# Nestling_2_1_EXB_MPU6050.net
KiCad netlist of a schematic drawn in Altium Designer
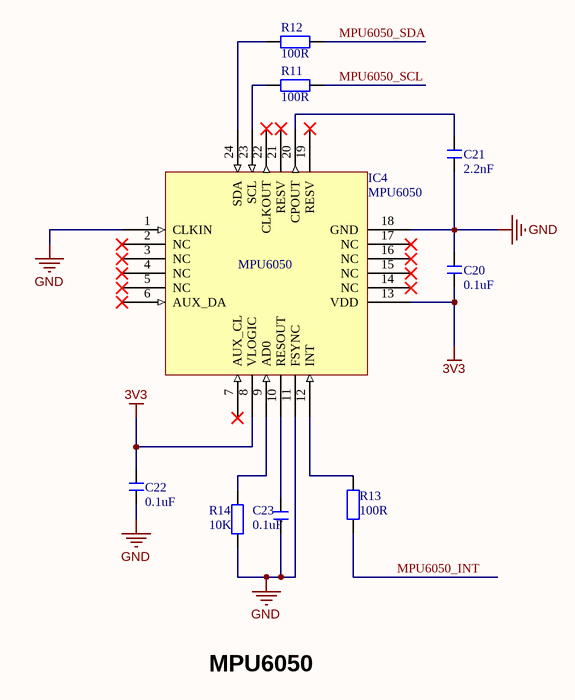
[diagram p0: Nestling_2.1_EXB_MPU6050.SchDoc]

(export (version "E")
  (design (tool "Eeschema 10.0.6"))
  (components
    (comp (ref "C20")
      (value "0.1uF")
      (footprint "C 0603_M")
      (description "无极性贴片电容")
      (fields (field (name "版权归属") "源创客"))
      (libsource (lib "altium-import") (part "root_3_C_"))
    )
    (comp (ref "C21")
      (value "2.2nF")
      (footprint "C 0603_M")
      (description "无极性贴片电容")
      (fields (field (name "版权归属") "源创客"))
      (libsource (lib "altium-import") (part "root_3_C_"))
    )
    (comp (ref "C22")
      (value "0.1uF")
      (footprint "C 0603_M")
      (description "无极性贴片电容")
      (fields (field (name "版权归属") "源创客"))
      (libsource (lib "altium-import") (part "root_3_C_"))
    )
    (comp (ref "C23")
      (value "0.1uF")
      (footprint "C 0603_M")
      (description "无极性贴片电容")
      (fields (field (name "版权归属") "源创客"))
      (libsource (lib "altium-import") (part "root_3_C_"))
    )
    (comp (ref "IC4")
      (value "MPU6050")
      (footprint "QFN24 4x4_N")
      (libsource (lib "altium-import") (part "root_0_MPU6050_"))
    )
    (comp (ref "R11")
      (value "100R")
      (footprint "R 0603_M")
      (description "Resistor")
      (libsource (lib "") (part "RES_1"))
    )
    (comp (ref "R12")
      (value "100R")
      (footprint "R 0603_M")
      (description "Resistor")
      (libsource (lib "") (part "RES_1"))
    )
    (comp (ref "R13")
      (value "100R")
      (footprint "R 0603_M")
      (description "Resistor")
      (libsource (lib "General") (part "RES"))
    )
    (comp (ref "R14")
      (value "10K")
      (footprint "R 0603_M")
      (description "Resistor")
      (libsource (lib "") (part "RES_2"))
    )
  )
  (nets
    (net (code "1") (name "/MPU6050_INT") (class "Default")
      (node (ref "R13") (pin "1") (pinfunction "1_1") (pintype "passive"))
    )
    (net (code "2") (name "/MPU6050_SCL") (class "Default")
      (node (ref "R11") (pin "1") (pinfunction "1_1") (pintype "passive"))
    )
    (net (code "3") (name "/MPU6050_SDA") (class "Default")
      (node (ref "R12") (pin "1") (pinfunction "1_1") (pintype "passive"))
    )
    (net (code "4") (name "3V3") (class "Default")
      (node (ref "C20") (pin "2") (pinfunction "2_2") (pintype "passive"))
      (node (ref "C22") (pin "1") (pinfunction "1_1") (pintype "passive"))
      (node (ref "IC4") (pin "13") (pinfunction "VDD_13") (pintype "power_in"))
      (node (ref "IC4") (pin "8") (pinfunction "VLOGIC_8") (pintype "passive"))
    )
    (net (code "5") (name "GND") (class "Default")
      (node (ref "C20") (pin "1") (pinfunction "1_1") (pintype "passive"))
      (node (ref "C21") (pin "2") (pinfunction "2_2") (pintype "passive"))
      (node (ref "C22") (pin "2") (pinfunction "2_2") (pintype "passive"))
      (node (ref "C23") (pin "2") (pinfunction "2_2") (pintype "passive"))
      (node (ref "IC4") (pin "1") (pinfunction "CLKIN_1") (pintype "input"))
      (node (ref "IC4") (pin "11") (pinfunction "FSYNC_11") (pintype "passive"))
      (node (ref "IC4") (pin "18") (pinfunction "GND_18") (pintype "power_in"))
      (node (ref "R14") (pin "2") (pinfunction "2_2") (pintype "passive"))
    )
    (net (code "6") (name "Net-(IC4-AD0)") (class "Default")
      (node (ref "IC4") (pin "9") (pinfunction "AD0_9") (pintype "input"))
      (node (ref "R14") (pin "1") (pinfunction "1_1") (pintype "passive"))
    )
    (net (code "7") (name "Net-(IC4-CPOUT)") (class "Default")
      (node (ref "C21") (pin "1") (pinfunction "1_1") (pintype "passive"))
      (node (ref "IC4") (pin "20") (pinfunction "CPOUT_20") (pintype "output"))
    )
    (net (code "8") (name "Net-(IC4-INT)") (class "Default")
      (node (ref "IC4") (pin "12") (pinfunction "INT_12") (pintype "input"))
      (node (ref "R13") (pin "2") (pinfunction "2_2") (pintype "passive"))
    )
    (net (code "9") (name "Net-(IC4-RESOUT)") (class "Default")
      (node (ref "C23") (pin "1") (pinfunction "1_1") (pintype "passive"))
      (node (ref "IC4") (pin "10") (pinfunction "RESOUT_10") (pintype "passive"))
    )
    (net (code "10") (name "Net-(IC4-SCL)") (class "Default")
      (node (ref "IC4") (pin "23") (pinfunction "SCL_23") (pintype "input"))
      (node (ref "R11") (pin "2") (pinfunction "2_2") (pintype "passive"))
    )
    (net (code "11") (name "Net-(IC4-SDA)") (class "Default")
      (node (ref "IC4") (pin "24") (pinfunction "SDA_24") (pintype "input"))
      (node (ref "R12") (pin "2") (pinfunction "2_2") (pintype "passive"))
    )
    (net (code "12") (name "unconnected-(IC4-AUX_CL-Pad7)") (class "Default")
      (node (ref "IC4") (pin "7") (pinfunction "AUX_CL_7") (pintype "input+no_connect"))
    )
    (net (code "13") (name "unconnected-(IC4-AUX_DA-Pad6)") (class "Default")
      (node (ref "IC4") (pin "6") (pinfunction "AUX_DA_6") (pintype "input+no_connect"))
    )
    (net (code "14") (name "unconnected-(IC4-CLKOUT-Pad22)") (class "Default")
      (node (ref "IC4") (pin "22") (pinfunction "CLKOUT_22") (pintype "output+no_connect"))
    )
    (net (code "15") (name "unconnected-(IC4-NC-Pad2)") (class "Default")
      (node (ref "IC4") (pin "2") (pinfunction "NC_2") (pintype "passive+no_connect"))
    )
    (net (code "16") (name "unconnected-(IC4-NC-Pad3)") (class "Default")
      (node (ref "IC4") (pin "3") (pinfunction "NC_3") (pintype "passive+no_connect"))
    )
    (net (code "17") (name "unconnected-(IC4-NC-Pad4)") (class "Default")
      (node (ref "IC4") (pin "4") (pinfunction "NC_4") (pintype "passive+no_connect"))
    )
    (net (code "18") (name "unconnected-(IC4-NC-Pad5)") (class "Default")
      (node (ref "IC4") (pin "5") (pinfunction "NC_5") (pintype "passive+no_connect"))
    )
    (net (code "19") (name "unconnected-(IC4-NC-Pad14)") (class "Default")
      (node (ref "IC4") (pin "14") (pinfunction "NC_14") (pintype "passive+no_connect"))
    )
    (net (code "20") (name "unconnected-(IC4-NC-Pad15)") (class "Default")
      (node (ref "IC4") (pin "15") (pinfunction "NC_15") (pintype "passive+no_connect"))
    )
    (net (code "21") (name "unconnected-(IC4-NC-Pad16)") (class "Default")
      (node (ref "IC4") (pin "16") (pinfunction "NC_16") (pintype "passive+no_connect"))
    )
    (net (code "22") (name "unconnected-(IC4-NC-Pad17)") (class "Default")
      (node (ref "IC4") (pin "17") (pinfunction "NC_17") (pintype "passive+no_connect"))
    )
    (net (code "23") (name "unconnected-(IC4-RESV-Pad19)") (class "Default")
      (node (ref "IC4") (pin "19") (pinfunction "RESV_19") (pintype "passive+no_connect"))
    )
    (net (code "24") (name "unconnected-(IC4-RESV-Pad21)") (class "Default")
      (node (ref "IC4") (pin "21") (pinfunction "RESV_21") (pintype "passive+no_connect"))
    )
  )
)
